# NE556-CD4069-Synth-Toy.net
KiCad netlist of a schematic drawn in EAGLE
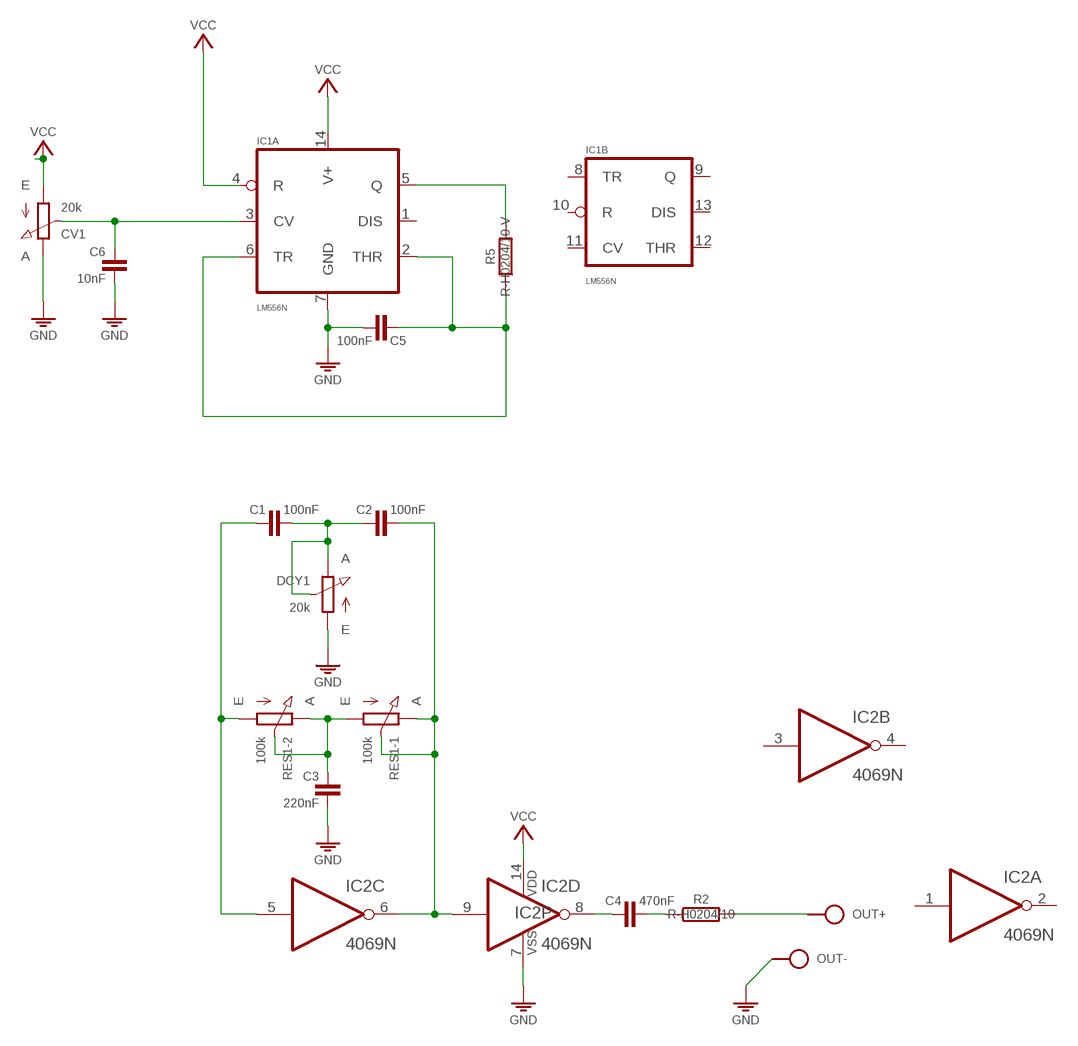
[diagram p0: schematic, sheet 1]

(export (version "E")
  (design (tool "Eeschema 10.0.6"))
  (components
    (comp (ref "C1")
      (value "100nF")
      (footprint "eagle-import:C050-024X044")
      (libsource (lib "eagle-import") (part "C-H050-024X044"))
    )
    (comp (ref "C2")
      (value "100nF")
      (footprint "eagle-import:C050-024X044")
      (libsource (lib "eagle-import") (part "C-H050-024X044"))
    )
    (comp (ref "C3")
      (value "220nF")
      (footprint "eagle-import:C050-020X044_V")
      (libsource (lib "eagle-import") (part "C050-020X044/V"))
    )
    (comp (ref "C4")
      (value "470nF")
      (footprint "eagle-import:C050-024X044")
      (libsource (lib "eagle-import") (part "C-H050-024X044"))
    )
    (comp (ref "C5")
      (value "100nF")
      (footprint "eagle-import:C050-020X044")
      (libsource (lib "eagle-import") (part "C-H050-020X044"))
    )
    (comp (ref "C6")
      (value "10nF")
      (footprint "eagle-import:C050-020X044_V")
      (libsource (lib "eagle-import") (part "C050-020X044/V"))
    )
    (comp (ref "CV1")
      (value "20k")
      (footprint "eagle-import:POT")
      (libsource (lib "eagle-import") (part "POT"))
    )
    (comp (ref "DCY1")
      (value "20k")
      (footprint "eagle-import:POT")
      (libsource (lib "eagle-import") (part "POT"))
    )
    (comp (ref "IC1")
      (value "LM556N")
      (footprint "eagle-import:DIL14")
      (libsource (lib "eagle-import") (part "556NLM"))
    )
    (comp (ref "IC2")
      (value "4069N")
      (footprint "eagle-import:DIL14")
      (libsource (lib "eagle-import") (part "4069N"))
    )
    (comp (ref "OUT")
      (value "SPAD+-+-")
      (footprint "eagle-import:SPAD+-")
      (libsource (lib "eagle-import") (part "SPAD+-+-"))
    )
    (comp (ref "R2")
      (value "R-H0204/10")
      (footprint "eagle-import:0204_10")
      (libsource (lib "eagle-import") (part "R-H0204/10"))
    )
    (comp (ref "R5")
      (value "R-H0204/10-V")
      (footprint "eagle-import:0204_10-V")
      (libsource (lib "eagle-import") (part "R-H0204/10-V"))
    )
    (comp (ref "RES1")
      (value "100k")
      (footprint "eagle-import:POT-STEREO-2X3")
      (libsource (lib "eagle-import") (part "POT-STEREO"))
    )
    (comp (ref "S3")
      (value "VCC_GNDPWR-L")
      (footprint "eagle-import:PWR-L")
      (libsource (lib "eagle-import") (part "VCC_GNDPWR-L"))
    )
  )
  (nets
    (net (code "1") (name "GND") (class "Default")
      (node (ref "C3") (pin "2") (pinfunction "2_2") (pintype "passive"))
      (node (ref "C5") (pin "2") (pinfunction "2_2") (pintype "passive"))
      (node (ref "C6") (pin "2") (pinfunction "2_2") (pintype "passive"))
      (node (ref "CV1") (pin "E") (pinfunction "E_E") (pintype "passive"))
      (node (ref "DCY1") (pin "A") (pinfunction "A_A") (pintype "passive"))
      (node (ref "IC1") (pin "7") (pinfunction "GND_7") (pintype "power_in"))
      (node (ref "IC2") (pin "7") (pinfunction "VSS_7") (pintype "power_in"))
      (node (ref "OUT") (pin "1") (pinfunction "P$1_1") (pintype "passive"))
      (node (ref "S3") (pin "1") (pinfunction "GND_1") (pintype "power_in"))
    )
    (net (code "2") (name "Net-(C1-Pad2)") (class "Default")
      (node (ref "C1") (pin "2") (pinfunction "2_2") (pintype "passive"))
      (node (ref "C2") (pin "1") (pinfunction "1_1") (pintype "passive"))
      (node (ref "DCY1") (pin "E") (pinfunction "E_E") (pintype "passive"))
      (node (ref "DCY1") (pin "S") (pinfunction "S_S") (pintype "passive"))
    )
    (net (code "3") (name "Net-(C4-Pad2)") (class "Default")
      (node (ref "C4") (pin "2") (pinfunction "2_2") (pintype "passive"))
      (node (ref "R2") (pin "1") (pinfunction "1_1") (pintype "passive"))
    )
    (net (code "4") (name "Net-(IC1A-CV)") (class "Default")
      (node (ref "C6") (pin "1") (pinfunction "1_1") (pintype "passive"))
      (node (ref "CV1") (pin "S") (pinfunction "S_S") (pintype "passive"))
      (node (ref "IC1") (pin "3") (pinfunction "CV_3") (pintype "input"))
    )
    (net (code "5") (name "Net-(IC1A-Q)") (class "Default")
      (node (ref "IC1") (pin "5") (pinfunction "Q_5") (pintype "output"))
      (node (ref "R5") (pin "2") (pinfunction "2_2") (pintype "passive"))
    )
    (net (code "6") (name "Net-(IC1A-THR)") (class "Default")
      (node (ref "C5") (pin "1") (pinfunction "1_1") (pintype "passive"))
      (node (ref "IC1") (pin "2") (pinfunction "THR_2") (pintype "input"))
      (node (ref "IC1") (pin "6") (pinfunction "TR_6") (pintype "input"))
      (node (ref "R5") (pin "1") (pinfunction "1_1") (pintype "passive"))
    )
    (net (code "7") (name "Net-(IC2C-I)") (class "Default")
      (node (ref "C1") (pin "1") (pinfunction "1_1") (pintype "passive"))
      (node (ref "IC2") (pin "5") (pinfunction "I_5") (pintype "input"))
      (node (ref "RES1") (pin "2-A") (pinfunction "A_2-A") (pintype "passive"))
    )
    (net (code "8") (name "Net-(IC2C-O)") (class "Default")
      (node (ref "C2") (pin "2") (pinfunction "2_2") (pintype "passive"))
      (node (ref "IC2") (pin "6") (pinfunction "O_6") (pintype "output"))
      (node (ref "IC2") (pin "9") (pinfunction "I_9") (pintype "input"))
      (node (ref "RES1") (pin "1-E") (pinfunction "E_1-E") (pintype "passive"))
      (node (ref "RES1") (pin "1-S") (pinfunction "S_1-S") (pintype "passive"))
    )
    (net (code "9") (name "Net-(IC2D-O)") (class "Default")
      (node (ref "C4") (pin "1") (pinfunction "1_1") (pintype "passive"))
      (node (ref "IC2") (pin "8") (pinfunction "O_8") (pintype "output"))
    )
    (net (code "10") (name "Net-(OUTA-P$1)") (class "Default")
      (node (ref "OUT") (pin "2") (pinfunction "P$1_2") (pintype "passive"))
      (node (ref "R2") (pin "2") (pinfunction "2_2") (pintype "passive"))
    )
    (net (code "11") (name "Net-(RES1A-A)") (class "Default")
      (node (ref "C3") (pin "1") (pinfunction "1_1") (pintype "passive"))
      (node (ref "RES1") (pin "1-A") (pinfunction "A_1-A") (pintype "passive"))
      (node (ref "RES1") (pin "2-E") (pinfunction "E_2-E") (pintype "passive"))
      (node (ref "RES1") (pin "2-S") (pinfunction "S_2-S") (pintype "passive"))
    )
    (net (code "12") (name "VCC") (class "Default")
      (node (ref "CV1") (pin "A") (pinfunction "A_A") (pintype "passive"))
      (node (ref "IC1") (pin "14") (pinfunction "V+_14") (pintype "power_in"))
      (node (ref "IC1") (pin "4") (pinfunction "R_4") (pintype "input"))
      (node (ref "IC2") (pin "14") (pinfunction "VDD_14") (pintype "power_in"))
      (node (ref "S3") (pin "2") (pinfunction "VCC_2") (pintype "power_in"))
    )
    (net (code "13") (name "unconnected-(IC1A-DIS-Pad1)") (class "Default")
      (node (ref "IC1") (pin "1") (pinfunction "DIS_1") (pintype "passive"))
    )
    (net (code "14") (name "unconnected-(IC1B-CV-Pad11)") (class "Default")
      (node (ref "IC1") (pin "11") (pinfunction "CV_11") (pintype "input"))
    )
    (net (code "15") (name "unconnected-(IC1B-DIS-Pad13)") (class "Default")
      (node (ref "IC1") (pin "13") (pinfunction "DIS_13") (pintype "input"))
    )
    (net (code "16") (name "unconnected-(IC1B-Q-Pad9)") (class "Default")
      (node (ref "IC1") (pin "9") (pinfunction "Q_9") (pintype "output"))
    )
    (net (code "17") (name "unconnected-(IC1B-R-Pad10)") (class "Default")
      (node (ref "IC1") (pin "10") (pinfunction "R_10") (pintype "input"))
    )
    (net (code "18") (name "unconnected-(IC1B-THR-Pad12)") (class "Default")
      (node (ref "IC1") (pin "12") (pinfunction "THR_12") (pintype "input"))
    )
    (net (code "19") (name "unconnected-(IC1B-TR-Pad8)") (class "Default")
      (node (ref "IC1") (pin "8") (pinfunction "TR_8") (pintype "input"))
    )
    (net (code "20") (name "unconnected-(IC2A-I-Pad1)") (class "Default")
      (node (ref "IC2") (pin "1") (pinfunction "I_1") (pintype "input"))
    )
    (net (code "21") (name "unconnected-(IC2A-O-Pad2)") (class "Default")
      (node (ref "IC2") (pin "2") (pinfunction "O_2") (pintype "output"))
    )
    (net (code "22") (name "unconnected-(IC2B-I-Pad3)") (class "Default")
      (node (ref "IC2") (pin "3") (pinfunction "I_3") (pintype "input"))
    )
    (net (code "23") (name "unconnected-(IC2B-O-Pad4)") (class "Default")
      (node (ref "IC2") (pin "4") (pinfunction "O_4") (pintype "output"))
    )
  )
)
